# design.net
KiCad netlist of a schematic drawn in Altium Designer
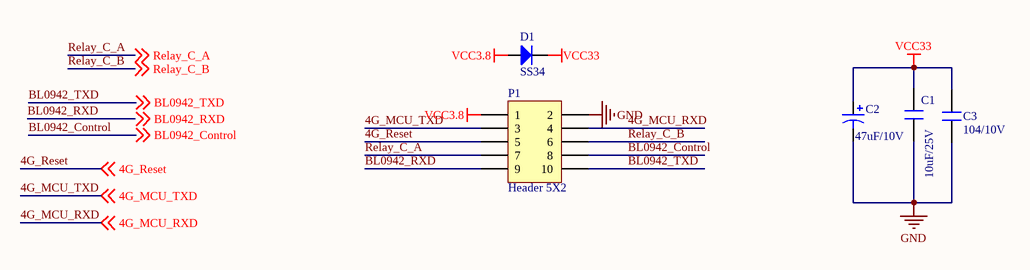
[diagram p0: 连接.SchDoc]

(export (version "E")
  (design (tool "Eeschema 10.0.6"))
  (components
    (comp (ref "C1") (value "10uF/25V") (footprint "0603R") (libsource (lib "ES_Schematic") (part "CAP")))
    (comp (ref "C2")
      (value "47uF/10V")
      (footprint "0805R")
      (description "Polarized Capacitor (Radial)")
      (fields (field (name "PUBLISHER") "Altium Limited"))
      (libsource (lib "Miscellaneous Devices") (part "Cap Pol1"))
    )
    (comp (ref "C3") (value "104/10V") (footprint "0603R") (libsource (lib "ES_Schematic") (part "CAP_1")))
    (comp (ref "D1") (value "SS34") (footprint "DO-214AC") (libsource (lib "ES_Schematic") (part "DIODE")))
    (comp (ref "P1")
      (value "Header 5X2")
      (footprint "HDR2X5")
      (description "Header, 5-Pin, Dual row")
      (fields (field (name "PUBLISHER") "Altium Limited"))
      (libsource (lib "Miscellaneous Connectors") (part "Header 5X2"))
    )
  )
  (nets
    (net (code "1") (name "4G_MCU_RXD") (class "Default")
      (node (ref "P1") (pin "4") (pinfunction "4_4") (pintype "passive"))
    )
    (net (code "2") (name "4G_MCU_TXD") (class "Default")
      (node (ref "P1") (pin "3") (pinfunction "3_3") (pintype "passive"))
    )
    (net (code "3") (name "4G_Reset") (class "Default")
      (node (ref "P1") (pin "5") (pinfunction "5_5") (pintype "passive"))
    )
    (net (code "4") (name "BL0942_Control") (class "Default")
      (node (ref "P1") (pin "8") (pinfunction "8_8") (pintype "passive"))
    )
    (net (code "5") (name "BL0942_RXD") (class "Default")
      (node (ref "P1") (pin "9") (pinfunction "9_9") (pintype "passive"))
    )
    (net (code "6") (name "BL0942_TXD") (class "Default")
      (node (ref "P1") (pin "10") (pinfunction "10_10") (pintype "passive"))
    )
    (net (code "7") (name "GND") (class "Default")
      (node (ref "C1") (pin "1") (pinfunction "1_1") (pintype "passive"))
      (node (ref "C2") (pin "2") (pinfunction "2_2") (pintype "passive"))
      (node (ref "C3") (pin "1") (pinfunction "1_1") (pintype "passive"))
      (node (ref "P1") (pin "2") (pinfunction "2_2") (pintype "passive"))
    )
    (net (code "8") (name "Relay_C_A") (class "Default")
      (node (ref "P1") (pin "7") (pinfunction "7_7") (pintype "passive"))
    )
    (net (code "9") (name "Relay_C_B") (class "Default")
      (node (ref "P1") (pin "6") (pinfunction "6_6") (pintype "passive"))
    )
    (net (code "10") (name "VCC3.8") (class "Default")
      (node (ref "D1") (pin "2") (pinfunction "A_2") (pintype "passive"))
      (node (ref "P1") (pin "1") (pinfunction "1_1") (pintype "passive"))
    )
    (net (code "11") (name "VCC33") (class "Default")
      (node (ref "C1") (pin "2") (pinfunction "2_2") (pintype "passive"))
      (node (ref "C2") (pin "1") (pinfunction "1_1") (pintype "passive"))
      (node (ref "C3") (pin "2") (pinfunction "2_2") (pintype "passive"))
      (node (ref "D1") (pin "1") (pinfunction "K_1") (pintype "passive"))
    )
  )
)
